# dechire.net
KiCad netlist of a schematic drawn in Altium Designer
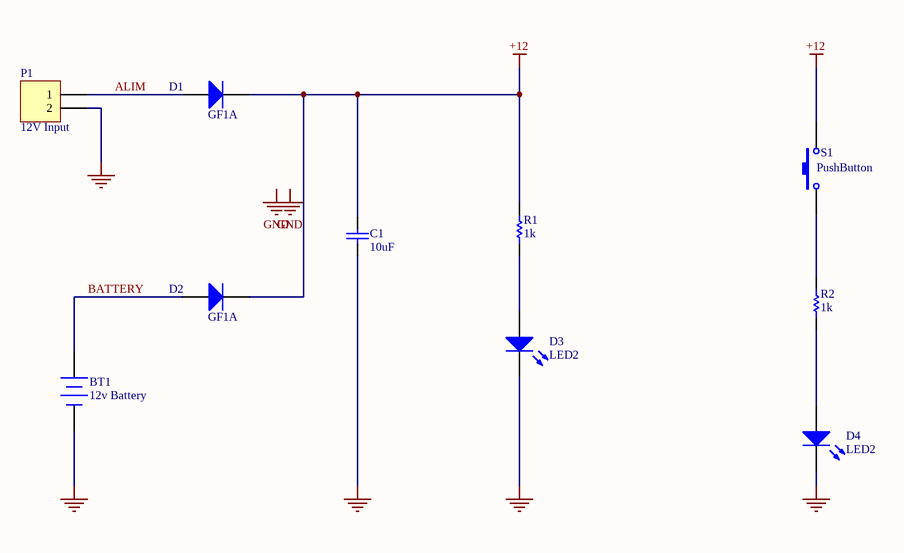
[diagram p0: dechire.SchDoc]

(export (version "E")
  (design (tool "Eeschema 10.0.6"))
  (components
    (comp (ref "BT1")
      (value "12v Battery")
      (footprint "BAT-2")
      (description "Multicell Battery")
      (fields (field (name "PUBLISHER") "Altium Limited"))
      (libsource (lib "Miscellaneous Devices") (part "Battery"))
    )
    (comp (ref "C1")
      (value "10uF")
      (footprint "RAD-0.3")
      (description "Capacitor")
      (fields (field (name "PUBLISHER") "Altium Limited"))
      (libsource (lib "Miscellaneous Devices") (part "Cap"))
    )
    (comp (ref "D1")
      (value "GF1A")
      (footprint "SMC")
      (description "Default Diode")
      (fields (field (name "PUBLISHER") "Altium Limited"))
      (libsource (lib "Miscellaneous Devices") (part "Diode"))
    )
    (comp (ref "D2")
      (value "GF1A")
      (footprint "SMC")
      (description "Default Diode")
      (fields (field (name "PUBLISHER") "Altium Limited"))
      (libsource (lib "Miscellaneous Devices") (part "Diode"))
    )
    (comp (ref "D3")
      (value "LED2")
      (footprint "LED-1")
      (description "Typical RED GaAs LED")
      (fields (field (name "PUBLISHER") "Altium Limited"))
      (libsource (lib "Miscellaneous Devices") (part "LED1"))
    )
    (comp (ref "D4")
      (value "LED2")
      (footprint "LED-1")
      (description "Typical RED GaAs LED")
      (fields (field (name "PUBLISHER") "Altium Limited"))
      (libsource (lib "Miscellaneous Devices") (part "LED1"))
    )
    (comp (ref "P1")
      (value "12V Input")
      (footprint "HDR1X2")
      (description "Header, 2-Pin")
      (fields (field (name "PUBLISHER") "Altium Limited"))
      (libsource (lib "Miscellaneous Connectors") (part "Header 2"))
    )
    (comp (ref "R1")
      (value "1k")
      (footprint "AXIAL-0.3")
      (description "Resistor")
      (fields (field (name "PUBLISHER") "Altium Limited"))
      (libsource (lib "Miscellaneous Devices") (part "Res1"))
    )
    (comp (ref "R2")
      (value "1k")
      (footprint "AXIAL-0.3")
      (description "Resistor")
      (fields (field (name "PUBLISHER") "Altium Limited"))
      (libsource (lib "Miscellaneous Devices") (part "Res1"))
    )
    (comp (ref "S1")
      (value "PushButton")
      (footprint "SPST-2")
      (description "Switch")
      (fields (field (name "PUBLISHER") "Altium Limited"))
      (libsource (lib "Miscellaneous Devices") (part "SW-PB"))
    )
  )
  (nets
    (net (code "1") (name "+12") (class "Default")
      (node (ref "C1") (pin "2") (pinfunction "2_2") (pintype "passive"))
      (node (ref "D1") (pin "2") (pinfunction "K_2") (pintype "passive"))
      (node (ref "D2") (pin "2") (pinfunction "K_2") (pintype "passive"))
      (node (ref "R1") (pin "2") (pinfunction "2_2") (pintype "passive"))
      (node (ref "S1") (pin "2") (pinfunction "2_2") (pintype "passive"))
    )
    (net (code "2") (name "/ALIM") (class "Default")
      (node (ref "D1") (pin "1") (pinfunction "A_1") (pintype "passive"))
      (node (ref "P1") (pin "1") (pinfunction "1_1") (pintype "passive"))
    )
    (net (code "3") (name "/BATTERY") (class "Default")
      (node (ref "BT1") (pin "1") (pinfunction "+_1") (pintype "passive"))
      (node (ref "D2") (pin "1") (pinfunction "A_1") (pintype "passive"))
    )
    (net (code "4") (name "GND") (class "Default")
      (node (ref "BT1") (pin "2") (pinfunction "-_2") (pintype "passive"))
      (node (ref "C1") (pin "1") (pinfunction "1_1") (pintype "passive"))
      (node (ref "D3") (pin "2") (pinfunction "K_2") (pintype "passive"))
      (node (ref "D4") (pin "2") (pinfunction "K_2") (pintype "passive"))
      (node (ref "P1") (pin "2") (pinfunction "2_2") (pintype "passive"))
    )
    (net (code "5") (name "Net-(D3-A)") (class "Default")
      (node (ref "D3") (pin "1") (pinfunction "A_1") (pintype "passive"))
      (node (ref "R1") (pin "1") (pinfunction "1_1") (pintype "passive"))
    )
    (net (code "6") (name "Net-(D4-A)") (class "Default")
      (node (ref "D4") (pin "1") (pinfunction "A_1") (pintype "passive"))
      (node (ref "R2") (pin "1") (pinfunction "1_1") (pintype "passive"))
    )
    (net (code "7") (name "Net-(R2-Pad2)") (class "Default")
      (node (ref "R2") (pin "2") (pinfunction "2_2") (pintype "passive"))
      (node (ref "S1") (pin "1") (pinfunction "1_1") (pintype "passive"))
    )
  )
)
